# strobe-pcb.net
KiCad netlist of a schematic drawn in EAGLE
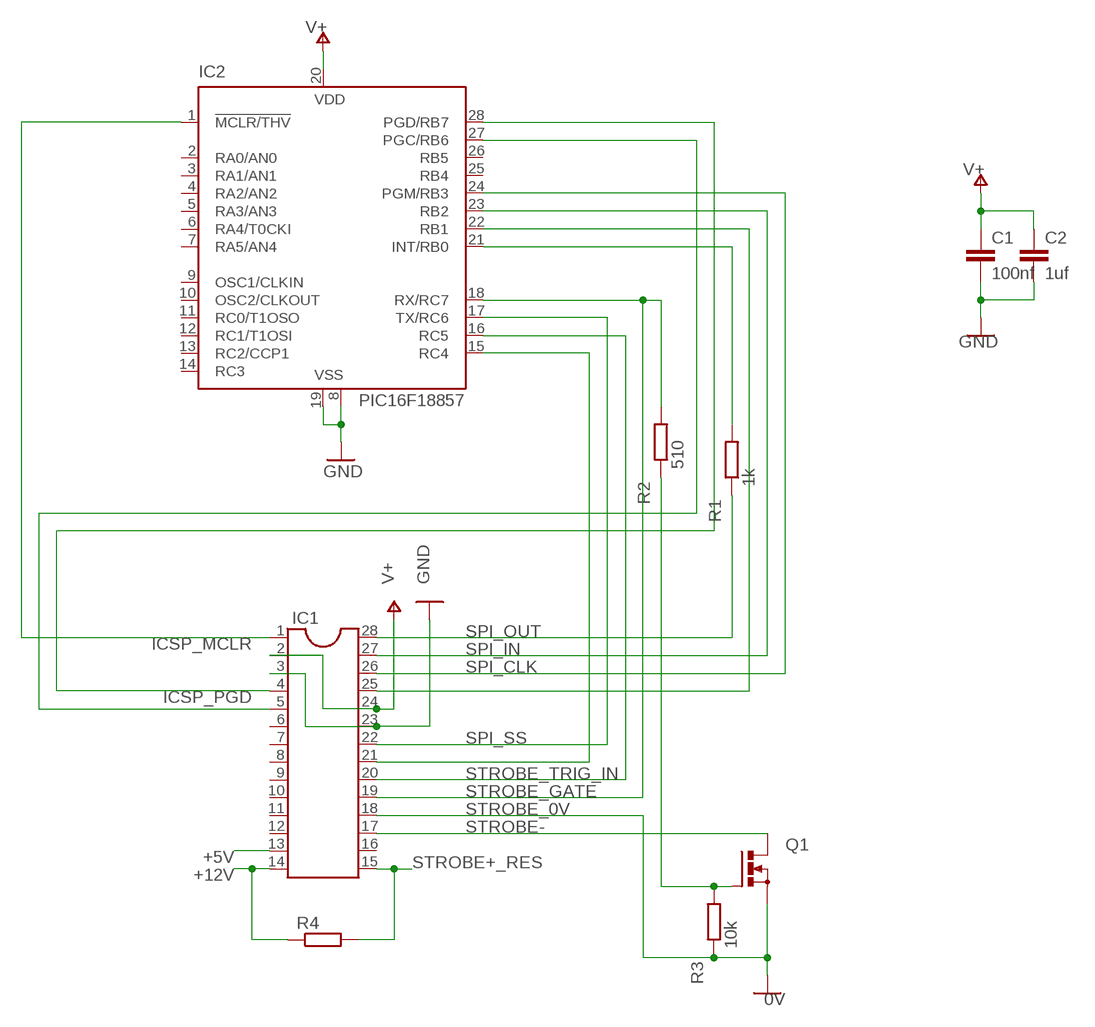
[diagram p0: schematic, sheet 1]

(export (version "E")
  (design (tool "Eeschema 10.0.6"))
  (components
    (comp (ref "C1")
      (value "100nf")
      (footprint "eagle-import:C1206")
      (libsource (lib "eagle-import") (part "C-EUC1206"))
    )
    (comp (ref "C2")
      (value "1uf")
      (footprint "eagle-import:C1206")
      (libsource (lib "eagle-import") (part "C-EUC1206"))
    )
    (comp (ref "IC1")
      (value "DIL28")
      (footprint "eagle-import:DIL28-6")
      (libsource (lib "eagle-import") (part "DIL28"))
    )
    (comp (ref "IC2")
      (value "PIC16F18857")
      (footprint "eagle-import:SO28W")
      (fields (field (name "MF") "MICROCHIP") (field (name "MPN") "PIC16F870-I/SO"))
      (libsource (lib "eagle-import") (part "PIC16870SOF"))
    )
    (comp (ref "Q1")
      (value "PMOSFET_NTO220BV")
      (footprint "eagle-import:TO220BV")
      (libsource (lib "eagle-import") (part "PMOSFET_NTO220BV"))
    )
    (comp (ref "R1")
      (value "1k")
      (footprint "eagle-import:R1206")
      (libsource (lib "eagle-import") (part "R-EU_R1206"))
    )
    (comp (ref "R2")
      (value "510")
      (footprint "eagle-import:R1206")
      (libsource (lib "eagle-import") (part "R-EU_R1206"))
    )
    (comp (ref "R3")
      (value "10k")
      (footprint "eagle-import:R1206")
      (libsource (lib "eagle-import") (part "R-EU_R1206"))
    )
    (comp (ref "R4")
      (value "R-EU_0207/10")
      (footprint "eagle-import:0207_10")
      (libsource (lib "eagle-import") (part "R-EU_0207/10"))
    )
  )
  (nets
    (net (code "1") (name "/+5V") (class "Default")
      (node (ref "IC1") (pin "13") (pinfunction "13_13") (pintype "passive"))
    )
    (net (code "2") (name "/+12V") (class "Default")
      (node (ref "IC1") (pin "14") (pinfunction "14_14") (pintype "passive"))
      (node (ref "R4") (pin "1") (pinfunction "1_1") (pintype "passive"))
    )
    (net (code "3") (name "/ICSP_MCLR") (class "Default")
      (node (ref "IC1") (pin "1") (pinfunction "1_1") (pintype "passive"))
      (node (ref "IC2") (pin "1") (pinfunction "~{MCLR/THV}_1") (pintype "input"))
    )
    (net (code "4") (name "/ICSP_PGD") (class "Default")
      (node (ref "IC1") (pin "4") (pinfunction "4_4") (pintype "passive"))
      (node (ref "IC2") (pin "28") (pinfunction "PGD/RB7_28") (pintype "bidirectional"))
    )
    (net (code "5") (name "/SPI_CLK") (class "Default")
      (node (ref "IC1") (pin "26") (pinfunction "26_26") (pintype "passive"))
      (node (ref "IC2") (pin "24") (pinfunction "PGM/RB3_24") (pintype "bidirectional"))
    )
    (net (code "6") (name "/SPI_IN") (class "Default")
      (node (ref "IC1") (pin "27") (pinfunction "27_27") (pintype "passive"))
      (node (ref "IC2") (pin "23") (pinfunction "RB2_23") (pintype "bidirectional"))
    )
    (net (code "7") (name "/SPI_OUT") (class "Default")
      (node (ref "IC1") (pin "28") (pinfunction "28_28") (pintype "passive"))
      (node (ref "R1") (pin "1") (pinfunction "1_1") (pintype "passive"))
    )
    (net (code "8") (name "/SPI_SS") (class "Default")
      (node (ref "IC1") (pin "22") (pinfunction "22_22") (pintype "passive"))
      (node (ref "IC2") (pin "17") (pinfunction "TX/RC6_17") (pintype "bidirectional"))
    )
    (net (code "9") (name "/STROBE+_RES") (class "Default")
      (node (ref "IC1") (pin "15") (pinfunction "15_15") (pintype "passive"))
      (node (ref "R4") (pin "2") (pinfunction "2_2") (pintype "passive"))
    )
    (net (code "10") (name "/STROBE-") (class "Default")
      (node (ref "IC1") (pin "17") (pinfunction "17_17") (pintype "passive"))
      (node (ref "Q1") (pin "D") (pinfunction "D_D") (pintype "passive"))
    )
    (net (code "11") (name "/STROBE_GATE") (class "Default")
      (node (ref "IC1") (pin "19") (pinfunction "19_19") (pintype "passive"))
      (node (ref "IC2") (pin "18") (pinfunction "RX/RC7_18") (pintype "bidirectional"))
      (node (ref "R2") (pin "2") (pinfunction "2_2") (pintype "passive"))
    )
    (net (code "12") (name "/STROBE_TRIG_IN") (class "Default")
      (node (ref "IC1") (pin "20") (pinfunction "20_20") (pintype "passive"))
      (node (ref "IC2") (pin "16") (pinfunction "RC5_16") (pintype "bidirectional"))
    )
    (net (code "13") (name "0V") (class "Default")
      (node (ref "IC1") (pin "18") (pinfunction "18_18") (pintype "passive"))
      (node (ref "Q1") (pin "S") (pinfunction "S_S") (pintype "passive"))
      (node (ref "R3") (pin "1") (pinfunction "1_1") (pintype "passive"))
    )
    (net (code "14") (name "GND") (class "Default")
      (node (ref "C1") (pin "2") (pinfunction "2_2") (pintype "passive"))
      (node (ref "C2") (pin "2") (pinfunction "2_2") (pintype "passive"))
      (node (ref "IC1") (pin "23") (pinfunction "23_23") (pintype "passive"))
      (node (ref "IC1") (pin "3") (pinfunction "3_3") (pintype "passive"))
      (node (ref "IC2") (pin "19") (pinfunction "VSS_19") (pintype "power_in"))
      (node (ref "IC2") (pin "8") (pinfunction "VSS_8") (pintype "power_in"))
    )
    (net (code "15") (name "Net-(IC2-INT{slash}RB0)") (class "Default")
      (node (ref "IC2") (pin "21") (pinfunction "INT/RB0_21") (pintype "bidirectional"))
      (node (ref "R1") (pin "2") (pinfunction "2_2") (pintype "passive"))
    )
    (net (code "16") (name "Net-(IC2-PGC{slash}RB6)") (class "Default")
      (node (ref "IC1") (pin "5") (pinfunction "5_5") (pintype "passive"))
      (node (ref "IC2") (pin "27") (pinfunction "PGC/RB6_27") (pintype "bidirectional"))
    )
    (net (code "17") (name "Net-(IC2-RB1)") (class "Default")
      (node (ref "IC1") (pin "25") (pinfunction "25_25") (pintype "passive"))
      (node (ref "IC2") (pin "22") (pinfunction "RB1_22") (pintype "bidirectional"))
    )
    (net (code "18") (name "Net-(IC2-RC4)") (class "Default")
      (node (ref "IC1") (pin "21") (pinfunction "21_21") (pintype "passive"))
      (node (ref "IC2") (pin "15") (pinfunction "RC4_15") (pintype "bidirectional"))
    )
    (net (code "19") (name "Net-(Q1-PadG)") (class "Default")
      (node (ref "Q1") (pin "G") (pinfunction "G_G") (pintype "passive"))
      (node (ref "R2") (pin "1") (pinfunction "1_1") (pintype "passive"))
      (node (ref "R3") (pin "2") (pinfunction "2_2") (pintype "passive"))
    )
    (net (code "20") (name "V+") (class "Default")
      (node (ref "C1") (pin "1") (pinfunction "1_1") (pintype "passive"))
      (node (ref "C2") (pin "1") (pinfunction "1_1") (pintype "passive"))
      (node (ref "IC1") (pin "2") (pinfunction "2_2") (pintype "passive"))
      (node (ref "IC1") (pin "24") (pinfunction "24_24") (pintype "passive"))
      (node (ref "IC2") (pin "20") (pinfunction "VDD_20") (pintype "power_in"))
    )
    (net (code "21") (name "unconnected-(IC1-Pad6)") (class "Default")
      (node (ref "IC1") (pin "6") (pinfunction "6_6") (pintype "passive"))
    )
    (net (code "22") (name "unconnected-(IC1-Pad7)") (class "Default")
      (node (ref "IC1") (pin "7") (pinfunction "7_7") (pintype "passive"))
    )
    (net (code "23") (name "unconnected-(IC1-Pad8)") (class "Default")
      (node (ref "IC1") (pin "8") (pinfunction "8_8") (pintype "passive"))
    )
    (net (code "24") (name "unconnected-(IC1-Pad9)") (class "Default")
      (node (ref "IC1") (pin "9") (pinfunction "9_9") (pintype "passive"))
    )
    (net (code "25") (name "unconnected-(IC1-Pad10)") (class "Default")
      (node (ref "IC1") (pin "10") (pinfunction "10_10") (pintype "passive"))
    )
    (net (code "26") (name "unconnected-(IC1-Pad11)") (class "Default")
      (node (ref "IC1") (pin "11") (pinfunction "11_11") (pintype "passive"))
    )
    (net (code "27") (name "unconnected-(IC1-Pad12)") (class "Default")
      (node (ref "IC1") (pin "12") (pinfunction "12_12") (pintype "passive"))
    )
    (net (code "28") (name "unconnected-(IC1-Pad16)") (class "Default")
      (node (ref "IC1") (pin "16") (pinfunction "16_16") (pintype "passive"))
    )
    (net (code "29") (name "unconnected-(IC2-OSC1{slash}CLKIN-Pad9)") (class "Default")
      (node (ref "IC2") (pin "9") (pinfunction "OSC1/CLKIN_9") (pintype "input"))
    )
    (net (code "30") (name "unconnected-(IC2-OSC2{slash}CLKOUT-Pad10)") (class "Default")
      (node (ref "IC2") (pin "10") (pinfunction "OSC2/CLKOUT_10") (pintype "output"))
    )
    (net (code "31") (name "unconnected-(IC2-RA0{slash}AN0-Pad2)") (class "Default")
      (node (ref "IC2") (pin "2") (pinfunction "RA0/AN0_2") (pintype "bidirectional"))
    )
    (net (code "32") (name "unconnected-(IC2-RA1{slash}AN1-Pad3)") (class "Default")
      (node (ref "IC2") (pin "3") (pinfunction "RA1/AN1_3") (pintype "bidirectional"))
    )
    (net (code "33") (name "unconnected-(IC2-RA2{slash}AN2-Pad4)") (class "Default")
      (node (ref "IC2") (pin "4") (pinfunction "RA2/AN2_4") (pintype "bidirectional"))
    )
    (net (code "34") (name "unconnected-(IC2-RA3{slash}AN3-Pad5)") (class "Default")
      (node (ref "IC2") (pin "5") (pinfunction "RA3/AN3_5") (pintype "bidirectional"))
    )
    (net (code "35") (name "unconnected-(IC2-RA4{slash}T0CKI-Pad6)") (class "Default")
      (node (ref "IC2") (pin "6") (pinfunction "RA4/T0CKI_6") (pintype "bidirectional"))
    )
    (net (code "36") (name "unconnected-(IC2-RA5{slash}AN4-Pad7)") (class "Default")
      (node (ref "IC2") (pin "7") (pinfunction "RA5/AN4_7") (pintype "bidirectional"))
    )
    (net (code "37") (name "unconnected-(IC2-RB4-Pad25)") (class "Default")
      (node (ref "IC2") (pin "25") (pinfunction "RB4_25") (pintype "bidirectional"))
    )
    (net (code "38") (name "unconnected-(IC2-RB5-Pad26)") (class "Default")
      (node (ref "IC2") (pin "26") (pinfunction "RB5_26") (pintype "bidirectional"))
    )
    (net (code "39") (name "unconnected-(IC2-RC0{slash}T1OSO-Pad11)") (class "Default")
      (node (ref "IC2") (pin "11") (pinfunction "RC0/T1OSO_11") (pintype "bidirectional"))
    )
    (net (code "40") (name "unconnected-(IC2-RC1{slash}T1OSI-Pad12)") (class "Default")
      (node (ref "IC2") (pin "12") (pinfunction "RC1/T1OSI_12") (pintype "bidirectional"))
    )
    (net (code "41") (name "unconnected-(IC2-RC2{slash}CCP1-Pad13)") (class "Default")
      (node (ref "IC2") (pin "13") (pinfunction "RC2/CCP1_13") (pintype "bidirectional"))
    )
    (net (code "42") (name "unconnected-(IC2-RC3-Pad14)") (class "Default")
      (node (ref "IC2") (pin "14") (pinfunction "RC3_14") (pintype "bidirectional"))
    )
  )
)
